# Display_adapter.net
KiCad netlist of a schematic drawn in EAGLE
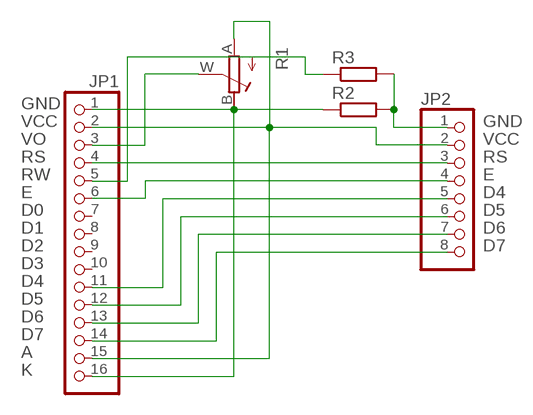
[diagram p0: schematic, sheet 1]

(export (version "E")
  (design (tool "Eeschema 10.0.6"))
  (components
    (comp (ref "JP1")
      (value "PINHD-1X16")
      (footprint "eagle-import:1X16")
      (libsource (lib "eagle-import") (part "PINHD-1X16"))
    )
    (comp (ref "JP2")
      (value "PINHD-1X8")
      (footprint "eagle-import:1X08")
      (libsource (lib "eagle-import") (part "PINHD-1X8"))
    )
    (comp (ref "R1")
      (value "R_POTTURN-X")
      (footprint "eagle-import:RJ9W")
      (libsource (lib "eagle-import") (part "R_POTTURN-X"))
    )
    (comp (ref "R2")
      (value "R_1206")
      (footprint "eagle-import:R1206")
      (libsource (lib "eagle-import") (part "R_1206"))
    )
    (comp (ref "R3")
      (value "R_1206")
      (footprint "eagle-import:R1206")
      (libsource (lib "eagle-import") (part "R_1206"))
    )
  )
  (nets
    (net (code "1") (name "Net-(JP1-Pad4)") (class "Default")
      (node (ref "JP1") (pin "4") (pinfunction "4_4") (pintype "passive"))
      (node (ref "JP2") (pin "3") (pinfunction "3_3") (pintype "passive"))
    )
    (net (code "2") (name "Net-(JP1-Pad5)") (class "Default")
      (node (ref "JP1") (pin "5") (pinfunction "5_5") (pintype "passive"))
      (node (ref "R3") (pin "1") (pinfunction "1_1") (pintype "passive"))
    )
    (net (code "3") (name "Net-(JP1-Pad6)") (class "Default")
      (node (ref "JP1") (pin "6") (pinfunction "6_6") (pintype "passive"))
      (node (ref "JP2") (pin "4") (pinfunction "4_4") (pintype "passive"))
    )
    (net (code "4") (name "Net-(JP1-Pad11)") (class "Default")
      (node (ref "JP1") (pin "11") (pinfunction "11_11") (pintype "passive"))
      (node (ref "JP2") (pin "5") (pinfunction "5_5") (pintype "passive"))
    )
    (net (code "5") (name "Net-(JP1-Pad12)") (class "Default")
      (node (ref "JP1") (pin "12") (pinfunction "12_12") (pintype "passive"))
      (node (ref "JP2") (pin "6") (pinfunction "6_6") (pintype "passive"))
    )
    (net (code "6") (name "Net-(JP1-Pad13)") (class "Default")
      (node (ref "JP1") (pin "13") (pinfunction "13_13") (pintype "passive"))
      (node (ref "JP2") (pin "7") (pinfunction "7_7") (pintype "passive"))
    )
    (net (code "7") (name "Net-(JP1-Pad14)") (class "Default")
      (node (ref "JP1") (pin "14") (pinfunction "14_14") (pintype "passive"))
      (node (ref "JP2") (pin "8") (pinfunction "8_8") (pintype "passive"))
    )
    (net (code "8") (name "Net-(JP1-Pad15)") (class "Default")
      (node (ref "JP1") (pin "15") (pinfunction "15_15") (pintype "passive"))
      (node (ref "JP1") (pin "2") (pinfunction "2_2") (pintype "passive"))
      (node (ref "JP2") (pin "2") (pinfunction "2_2") (pintype "passive"))
      (node (ref "R1") (pin "A") (pinfunction "A_A") (pintype "passive"))
    )
    (net (code "9") (name "Net-(JP2-Pad1)") (class "Default")
      (node (ref "JP2") (pin "1") (pinfunction "1_1") (pintype "passive"))
      (node (ref "R2") (pin "2") (pinfunction "2_2") (pintype "passive"))
      (node (ref "R3") (pin "2") (pinfunction "2_2") (pintype "passive"))
    )
    (net (code "10") (name "Net-(R1-E)") (class "Default")
      (node (ref "JP1") (pin "1") (pinfunction "1_1") (pintype "passive"))
      (node (ref "JP1") (pin "16") (pinfunction "16_16") (pintype "passive"))
      (node (ref "R1") (pin "B") (pinfunction "E_B") (pintype "passive"))
      (node (ref "R2") (pin "1") (pinfunction "1_1") (pintype "passive"))
    )
    (net (code "11") (name "Net-(R1-S)") (class "Default")
      (node (ref "JP1") (pin "3") (pinfunction "3_3") (pintype "passive"))
      (node (ref "R1") (pin "W") (pinfunction "S_W") (pintype "passive"))
    )
    (net (code "12") (name "unconnected-(JP1-Pad7)") (class "Default")
      (node (ref "JP1") (pin "7") (pinfunction "7_7") (pintype "passive"))
    )
    (net (code "13") (name "unconnected-(JP1-Pad8)") (class "Default")
      (node (ref "JP1") (pin "8") (pinfunction "8_8") (pintype "passive"))
    )
    (net (code "14") (name "unconnected-(JP1-Pad9)") (class "Default")
      (node (ref "JP1") (pin "9") (pinfunction "9_9") (pintype "passive"))
    )
    (net (code "15") (name "unconnected-(JP1-Pad10)") (class "Default")
      (node (ref "JP1") (pin "10") (pinfunction "10_10") (pintype "passive"))
    )
  )
)
